# Sheet1.net
KiCad netlist of a schematic drawn in Altium Designer
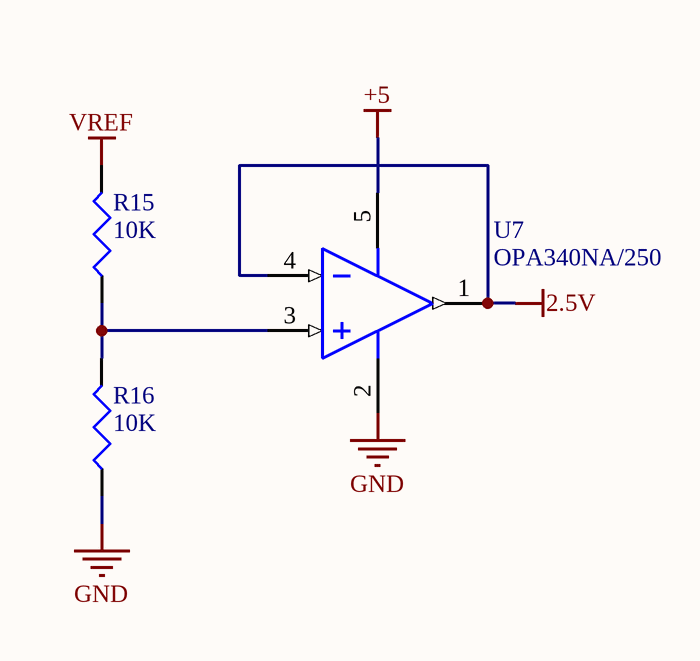
[diagram p0: Sheet1.SchDoc]

(export (version "E")
  (design (tool "Eeschema 10.0.6"))
  (components
    (comp (ref "R15") (value "10K") (footprint "R_0402") (libsource (lib "Mercury2") (part "RES_0402")))
    (comp (ref "R16") (value "10K") (footprint "R_0402") (libsource (lib "Mercury2") (part "RES_0402")))
    (comp (ref "U7")
      (value "OPA340NA/250")
      (footprint "DBV0005A_M")
      (fields (field (name "MANUFACTURER") "Texas Instruments"))
      (libsource (lib "Altium Content Vault") (part "TI-OPA_SM7XXXX-DBV5"))
    )
  )
  (nets
    (net (code "1") (name "+5") (class "Default")
      (node (ref "U7") (pin "5") (pinfunction "V+_5") (pintype "power_in"))
    )
    (net (code "2") (name "2.5V") (class "Default")
      (node (ref "U7") (pin "1") (pinfunction "OUT_1") (pintype "output"))
      (node (ref "U7") (pin "4") (pinfunction "IN-_4") (pintype "input"))
    )
    (net (code "3") (name "GND") (class "Default")
      (node (ref "R16") (pin "1") (pinfunction "1_1") (pintype "passive"))
      (node (ref "U7") (pin "2") (pinfunction "V-_2") (pintype "power_in"))
    )
    (net (code "4") (name "Net-(U7-IN+)") (class "Default")
      (node (ref "R15") (pin "1") (pinfunction "1_1") (pintype "passive"))
      (node (ref "R16") (pin "2") (pinfunction "2_2") (pintype "passive"))
      (node (ref "U7") (pin "3") (pinfunction "IN+_3") (pintype "input"))
    )
    (net (code "5") (name "VREF") (class "Default")
      (node (ref "R15") (pin "2") (pinfunction "2_2") (pintype "passive"))
    )
  )
)
